# 3_-MCU_MAIN.net
KiCad netlist of a schematic drawn in Altium Designer
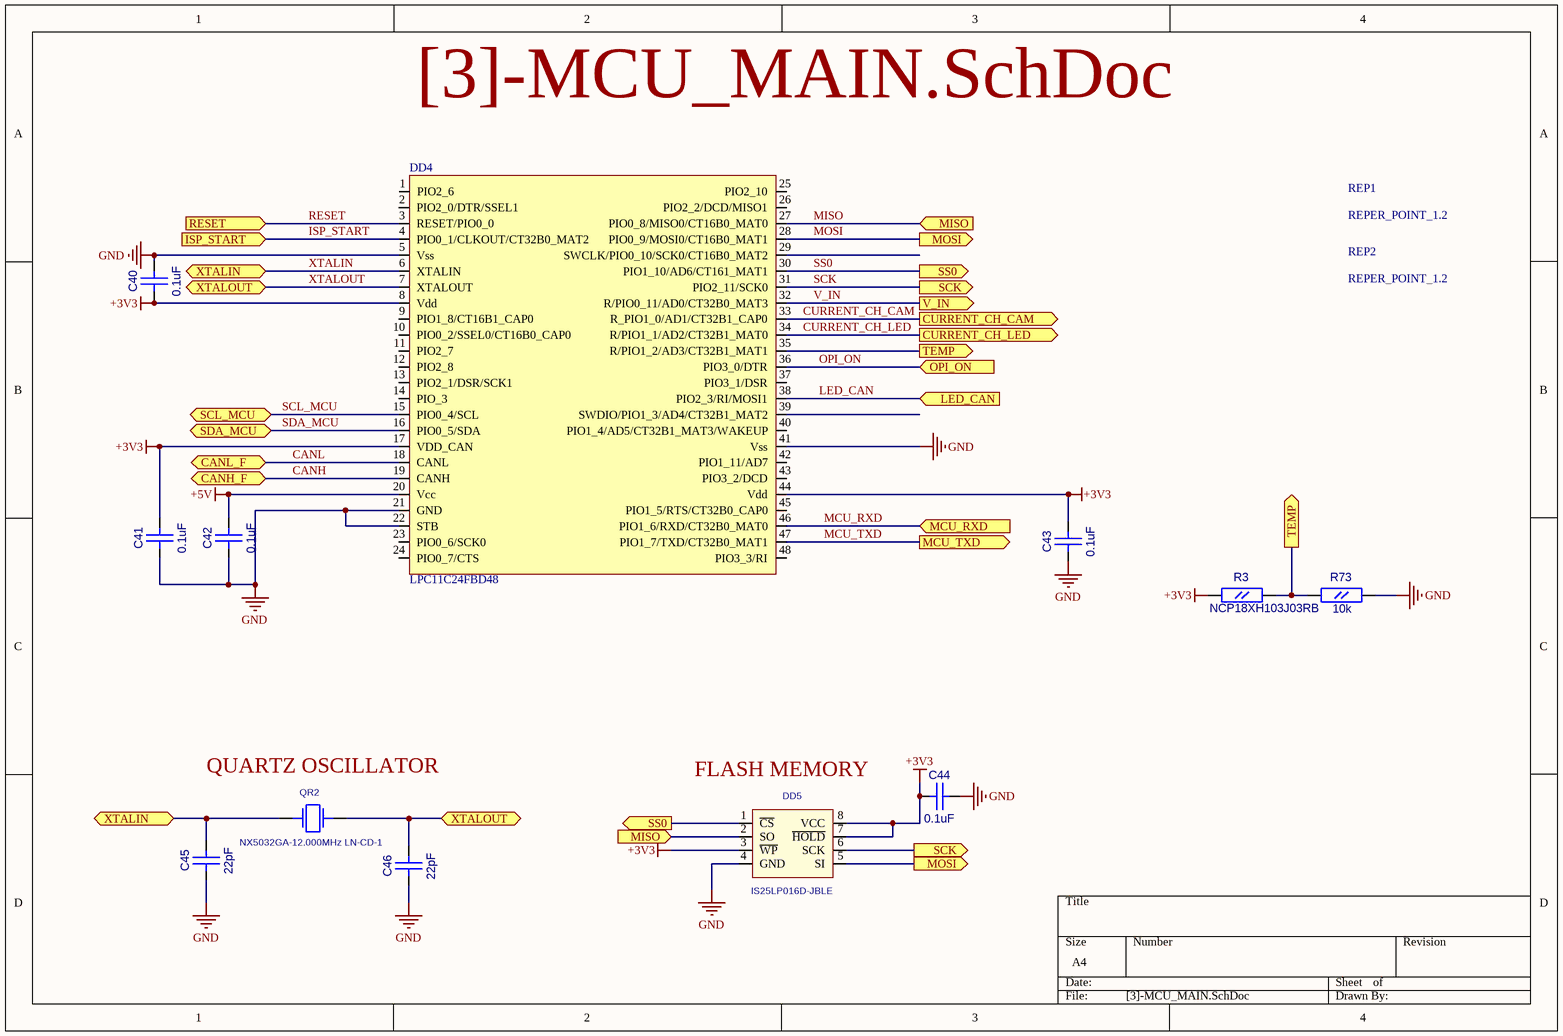
[diagram p0: [3]-MCU_MAIN.SchDoc]

(export (version "E")
  (design (tool "Eeschema 10.0.6"))
  (components
    (comp (ref "C40")
      (value "0.1uF")
      (footprint "CC0603")
      (description "CC0603")
      (libsource (lib "fizik_lib") (part "CC0603"))
    )
    (comp (ref "C41")
      (value "0.1uF")
      (footprint "CC0603")
      (description "CC0603")
      (libsource (lib "fizik_lib") (part "CC0603"))
    )
    (comp (ref "C42")
      (value "0.1uF")
      (footprint "CC0603")
      (description "CC0603")
      (libsource (lib "fizik_lib") (part "CC0603"))
    )
    (comp (ref "C43")
      (value "0.1uF")
      (footprint "CC0603")
      (description "CC0603")
      (libsource (lib "fizik_lib") (part "CC0603"))
    )
    (comp (ref "C44")
      (value "0.1uF")
      (footprint "CC0603")
      (description "CC0603")
      (libsource (lib "gprs_modem_2") (part "CC0603"))
    )
    (comp (ref "C45")
      (value "22pF")
      (footprint "CC0603")
      (description "CC0603")
      (libsource (lib "gprs_modem_2") (part "CC0603"))
    )
    (comp (ref "C46")
      (value "22pF")
      (footprint "CC0603")
      (description "CC0603")
      (libsource (lib "gprs_modem_2") (part "CC0603"))
    )
    (comp (ref "DD4")
      (value "LPC11C24FBD48")
      (footprint "LQFP48")
      (libsource (lib "fizik_lib") (part "LPC11C24FBD48"))
    )
    (comp (ref "DD5")
      (value "IS25LP016D-JBLE")
      (footprint "EIAJ_SO8")
      (description "S25FL016A0LMFI01")
      (libsource (lib "gprs_modem_2") (part "S25FL016A0LMFI01"))
    )
    (comp (ref "QR2")
      (value "NX5032GA-12.000MHz LN-CD-1")
      (footprint "AC5032_2")
      (description "AC5032/2")
      (libsource (lib "gprs_modem_2") (part "AC5032_2"))
    )
    (comp (ref "R3")
      (value "NCP18XH103J03RB")
      (footprint "RC0603")
      (description "RC0603")
      (libsource (lib "fizik_lib") (part "RC0603"))
    )
    (comp (ref "R73")
      (value "10k")
      (footprint "RC0603")
      (description "RC0603")
      (libsource (lib "fizik_lib") (part "RC0603"))
    )
    (comp (ref "REP1")
      (value "REPER_POINT_1.2")
      (footprint "REPER1.2")
      (description "REPER1.2")
      (libsource (lib "fizik_lib") (part "REPER1.2"))
    )
    (comp (ref "REP2")
      (value "REPER_POINT_1.2")
      (footprint "REPER1.2")
      (description "REPER1.2")
      (libsource (lib "fizik_lib") (part "REPER1.2"))
    )
  )
  (nets
    (net (code "1") (name "+3V3") (class "Default")
      (node (ref "C40") (pin "1") (pinfunction "A_1") (pintype "passive"))
      (node (ref "C41") (pin "2") (pinfunction "B_2") (pintype "passive"))
      (node (ref "C43") (pin "2") (pinfunction "B_2") (pintype "passive"))
      (node (ref "C44") (pin "1") (pinfunction "A_1") (pintype "passive"))
      (node (ref "DD4") (pin "17") (pinfunction "VDD_CAN_17") (pintype "passive"))
      (node (ref "DD4") (pin "44") (pinfunction "Vdd_44") (pintype "passive"))
      (node (ref "DD4") (pin "8") (pinfunction "Vdd_8") (pintype "passive"))
      (node (ref "DD5") (pin "3") (pinfunction "~{WP}_3") (pintype "passive"))
      (node (ref "DD5") (pin "7") (pinfunction "~{HOLD}_7") (pintype "passive"))
      (node (ref "DD5") (pin "8") (pinfunction "VCC_8") (pintype "passive"))
      (node (ref "R3") (pin "1") (pinfunction "A_1") (pintype "passive"))
    )
    (net (code "2") (name "+5V") (class "Default")
      (node (ref "C42") (pin "2") (pinfunction "B_2") (pintype "passive"))
      (node (ref "DD4") (pin "20") (pinfunction "Vcc_20") (pintype "passive"))
    )
    (net (code "3") (name "/CANH") (class "Default")
      (node (ref "DD4") (pin "19") (pinfunction "CANH_19") (pintype "passive"))
    )
    (net (code "4") (name "/CANL") (class "Default")
      (node (ref "DD4") (pin "18") (pinfunction "CANL_18") (pintype "passive"))
    )
    (net (code "5") (name "/CURRENT_CH_CAM") (class "Default")
      (node (ref "DD4") (pin "33") (pinfunction "R_PIO1_0/AD1/CT32B1_CAP0_33") (pintype "passive"))
    )
    (net (code "6") (name "/CURRENT_CH_LED") (class "Default")
      (node (ref "DD4") (pin "34") (pinfunction "R/PIO1_1/AD2/CT32B1_MAT0_34") (pintype "passive"))
    )
    (net (code "7") (name "/ISP_START") (class "Default")
      (node (ref "DD4") (pin "4") (pinfunction "PIO0_1/CLKOUT/CT32B0_MAT2_4") (pintype "passive"))
    )
    (net (code "8") (name "/LED_CAN") (class "Default")
      (node (ref "DD4") (pin "38") (pinfunction "PIO2_3/RI/MOSI1_38") (pintype "passive"))
    )
    (net (code "9") (name "/MCU_RXD") (class "Default")
      (node (ref "DD4") (pin "46") (pinfunction "PIO1_6/RXD/CT32B0_MAT0_46") (pintype "passive"))
    )
    (net (code "10") (name "/MCU_TXD") (class "Default")
      (node (ref "DD4") (pin "47") (pinfunction "PIO1_7/TXD/CT32B0_MAT1_47") (pintype "passive"))
    )
    (net (code "11") (name "/MISO") (class "Default")
      (node (ref "DD4") (pin "27") (pinfunction "PIO0_8/MISO0/CT16B0_MAT0_27") (pintype "passive"))
      (node (ref "DD5") (pin "2") (pinfunction "SO_2") (pintype "passive"))
    )
    (net (code "12") (name "/MOSI") (class "Default")
      (node (ref "DD4") (pin "28") (pinfunction "PIO0_9/MOSI0/CT16B0_MAT1_28") (pintype "passive"))
      (node (ref "DD5") (pin "5") (pinfunction "SI_5") (pintype "passive"))
    )
    (net (code "13") (name "/OPI_ON") (class "Default")
      (node (ref "DD4") (pin "36") (pinfunction "PIO3_0/DTR_36") (pintype "passive"))
    )
    (net (code "14") (name "/RESET") (class "Default")
      (node (ref "DD4") (pin "3") (pinfunction "RESET/PIO0_0_3") (pintype "passive"))
    )
    (net (code "15") (name "/SCK") (class "Default")
      (node (ref "DD4") (pin "31") (pinfunction "PIO2_11/SCK0_31") (pintype "passive"))
      (node (ref "DD5") (pin "6") (pinfunction "SCK_6") (pintype "passive"))
    )
    (net (code "16") (name "/SCL_MCU") (class "Default")
      (node (ref "DD4") (pin "15") (pinfunction "PIO0_4/SCL_15") (pintype "passive"))
    )
    (net (code "17") (name "/SDA_MCU") (class "Default")
      (node (ref "DD4") (pin "16") (pinfunction "PIO0_5/SDA_16") (pintype "passive"))
    )
    (net (code "18") (name "/SS0") (class "Default")
      (node (ref "DD4") (pin "30") (pinfunction "PIO1_10/AD6/CT161_MAT1_30") (pintype "passive"))
      (node (ref "DD5") (pin "1") (pinfunction "~{CS}_1") (pintype "passive"))
    )
    (net (code "19") (name "/TEMP") (class "Default")
      (node (ref "DD4") (pin "35") (pinfunction "R/PIO1_2/AD3/CT32B1_MAT1_35") (pintype "passive"))
      (node (ref "R3") (pin "2") (pinfunction "B_2") (pintype "passive"))
      (node (ref "R73") (pin "1") (pinfunction "A_1") (pintype "passive"))
    )
    (net (code "20") (name "/V_IN") (class "Default")
      (node (ref "DD4") (pin "32") (pinfunction "R/PIO0_11/AD0/CT32B0_MAT3_32") (pintype "passive"))
    )
    (net (code "21") (name "/XTALIN") (class "Default")
      (node (ref "C45") (pin "2") (pinfunction "B_2") (pintype "passive"))
      (node (ref "DD4") (pin "6") (pinfunction "XTALIN_6") (pintype "passive"))
      (node (ref "QR2") (pin "1") (pintype "passive"))
    )
    (net (code "22") (name "/XTALOUT") (class "Default")
      (node (ref "C46") (pin "2") (pinfunction "B_2") (pintype "passive"))
      (node (ref "DD4") (pin "7") (pinfunction "XTALOUT_7") (pintype "passive"))
      (node (ref "QR2") (pin "2") (pintype "passive"))
    )
    (net (code "23") (name "GND") (class "Default")
      (node (ref "C40") (pin "2") (pinfunction "B_2") (pintype "passive"))
      (node (ref "C41") (pin "1") (pinfunction "A_1") (pintype "passive"))
      (node (ref "C42") (pin "1") (pinfunction "A_1") (pintype "passive"))
      (node (ref "C43") (pin "1") (pinfunction "A_1") (pintype "passive"))
      (node (ref "C44") (pin "2") (pinfunction "B_2") (pintype "passive"))
      (node (ref "C45") (pin "1") (pinfunction "A_1") (pintype "passive"))
      (node (ref "C46") (pin "1") (pinfunction "A_1") (pintype "passive"))
      (node (ref "DD4") (pin "21") (pinfunction "GND_21") (pintype "passive"))
      (node (ref "DD4") (pin "22") (pinfunction "STB_22") (pintype "passive"))
      (node (ref "DD4") (pin "41") (pinfunction "Vss_41") (pintype "passive"))
      (node (ref "DD4") (pin "5") (pinfunction "Vss_5") (pintype "passive"))
      (node (ref "DD5") (pin "4") (pinfunction "GND_4") (pintype "passive"))
      (node (ref "R73") (pin "2") (pinfunction "B_2") (pintype "passive"))
    )
    (net (code "24") (name "unconnected-(DD4-PIO0_2{slash}SSEL0{slash}CT16B0_CAP0-Pad10)") (class "Default")
      (node (ref "DD4") (pin "10") (pinfunction "PIO0_2/SSEL0/CT16B0_CAP0_10") (pintype "passive"))
    )
    (net (code "25") (name "unconnected-(DD4-PIO0_6{slash}SCK0-Pad23)") (class "Default")
      (node (ref "DD4") (pin "23") (pinfunction "PIO0_6/SCK0_23") (pintype "passive"))
    )
    (net (code "26") (name "unconnected-(DD4-PIO0_7{slash}CTS-Pad24)") (class "Default")
      (node (ref "DD4") (pin "24") (pinfunction "PIO0_7/CTS_24") (pintype "passive"))
    )
    (net (code "27") (name "unconnected-(DD4-PIO1_4{slash}AD5{slash}CT32B1_MAT3{slash}WAKEUP-Pad40)") (class "Default")
      (node (ref "DD4") (pin "40") (pinfunction "PIO1_4/AD5/CT32B1_MAT3/WAKEUP_40") (pintype "passive"))
    )
    (net (code "28") (name "unconnected-(DD4-PIO1_5{slash}RTS{slash}CT32B0_CAP0-Pad45)") (class "Default")
      (node (ref "DD4") (pin "45") (pinfunction "PIO1_5/RTS/CT32B0_CAP0_45") (pintype "passive"))
    )
    (net (code "29") (name "unconnected-(DD4-PIO1_8{slash}CT16B1_CAP0-Pad9)") (class "Default")
      (node (ref "DD4") (pin "9") (pinfunction "PIO1_8/CT16B1_CAP0_9") (pintype "passive"))
    )
    (net (code "30") (name "unconnected-(DD4-PIO1_11{slash}AD7-Pad42)") (class "Default")
      (node (ref "DD4") (pin "42") (pinfunction "PIO1_11/AD7_42") (pintype "passive"))
    )
    (net (code "31") (name "unconnected-(DD4-PIO2_0{slash}DTR{slash}SSEL1-Pad2)") (class "Default")
      (node (ref "DD4") (pin "2") (pinfunction "PIO2_0/DTR/SSEL1_2") (pintype "passive"))
    )
    (net (code "32") (name "unconnected-(DD4-PIO2_1{slash}DSR{slash}SCK1-Pad13)") (class "Default")
      (node (ref "DD4") (pin "13") (pinfunction "PIO2_1/DSR/SCK1_13") (pintype "passive"))
    )
    (net (code "33") (name "unconnected-(DD4-PIO2_2{slash}DCD{slash}MISO1-Pad26)") (class "Default")
      (node (ref "DD4") (pin "26") (pinfunction "PIO2_2/DCD/MISO1_26") (pintype "passive"))
    )
    (net (code "34") (name "unconnected-(DD4-PIO2_6-Pad1)") (class "Default")
      (node (ref "DD4") (pin "1") (pinfunction "PIO2_6_1") (pintype "passive"))
    )
    (net (code "35") (name "unconnected-(DD4-PIO2_7-Pad11)") (class "Default")
      (node (ref "DD4") (pin "11") (pinfunction "PIO2_7_11") (pintype "passive"))
    )
    (net (code "36") (name "unconnected-(DD4-PIO2_8-Pad12)") (class "Default")
      (node (ref "DD4") (pin "12") (pinfunction "PIO2_8_12") (pintype "passive"))
    )
    (net (code "37") (name "unconnected-(DD4-PIO2_10-Pad25)") (class "Default")
      (node (ref "DD4") (pin "25") (pinfunction "PIO2_10_25") (pintype "passive"))
    )
    (net (code "38") (name "unconnected-(DD4-PIO3_1{slash}DSR-Pad37)") (class "Default")
      (node (ref "DD4") (pin "37") (pinfunction "PIO3_1/DSR_37") (pintype "passive"))
    )
    (net (code "39") (name "unconnected-(DD4-PIO3_2{slash}DCD-Pad43)") (class "Default")
      (node (ref "DD4") (pin "43") (pinfunction "PIO3_2/DCD_43") (pintype "passive"))
    )
    (net (code "40") (name "unconnected-(DD4-PIO3_3{slash}RI-Pad48)") (class "Default")
      (node (ref "DD4") (pin "48") (pinfunction "PIO3_3/RI_48") (pintype "passive"))
    )
    (net (code "41") (name "unconnected-(DD4-PIO_3-Pad14)") (class "Default")
      (node (ref "DD4") (pin "14") (pinfunction "PIO_3_14") (pintype "passive"))
    )
    (net (code "42") (name "unconnected-(DD4-SWCLK{slash}PIO0_10{slash}SCK0{slash}CT16B0_MAT2-Pad29)") (class "Default")
      (node (ref "DD4") (pin "29") (pinfunction "SWCLK/PIO0_10/SCK0/CT16B0_MAT2_29") (pintype "passive"))
    )
    (net (code "43") (name "unconnected-(DD4-SWDIO{slash}PIO1_3{slash}AD4{slash}CT32B1_MAT2-Pad39)") (class "Default")
      (node (ref "DD4") (pin "39") (pinfunction "SWDIO/PIO1_3/AD4/CT32B1_MAT2_39") (pintype "passive"))
    )
    (net (code "44") (name "unconnected-(REP1-Pad1)") (class "Default")
      (node (ref "REP1") (pin "1") (pintype "passive"))
    )
    (net (code "45") (name "unconnected-(REP2-Pad1)") (class "Default")
      (node (ref "REP2") (pin "1") (pintype "passive"))
    )
  )
)
